# DB_Main-X01.net
KiCad netlist of a schematic drawn in Altium Designer
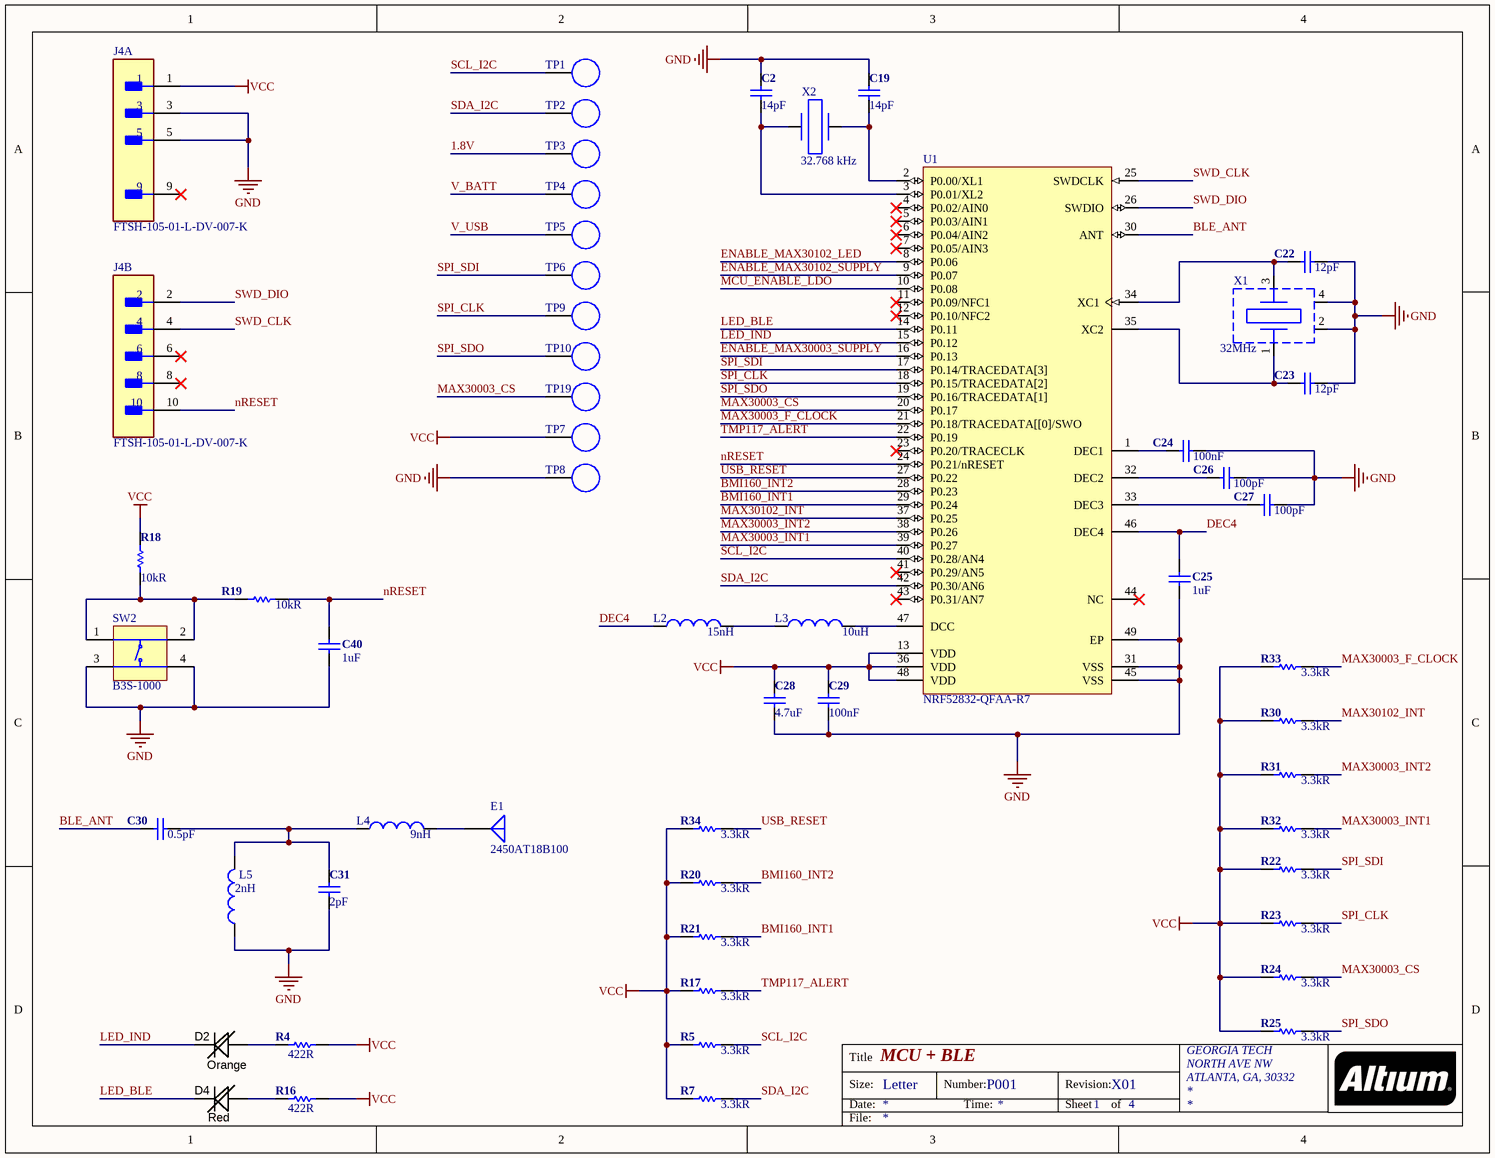
[diagram p0: DB_Main-X01.SchDoc]

(export (version "E")
  (design (tool "Eeschema 10.0.6"))
  (components
    (comp (ref "C2")
      (value "14pF")
      (footprint "C0402")
      (fields
        (field (name "MANUFACTURER") "Kyocera AVX")
        (field (name "MANUFACTURER PART NUMBER") "04025U140FAT2A")
        (field (name "TOLERANCE") "1%")
      )
      (libsource (lib "DB-X01") (part "C-0402(1005)"))
    )
    (comp (ref "C19")
      (value "14pF")
      (footprint "C0402")
      (fields
        (field (name "MANUFACTURER") "Kyocera AVX")
        (field (name "MANUFACTURER PART NUMBER") "04025U140FAT2A")
        (field (name "TOLERANCE") "1%")
      )
      (libsource (lib "DB-X01") (part "C-0402(1005)"))
    )
    (comp (ref "C22")
      (value "12pF")
      (footprint "C0402")
      (fields
        (field (name "MANUFACTURER") "Kyocera AVX")
        (field (name "MANUFACTURER PART NUMBER") "04025U120FAT2A")
        (field (name "TOLERANCE") "1%")
      )
      (libsource (lib "DB-X01") (part "C-0402(1005)"))
    )
    (comp (ref "C23")
      (value "12pF")
      (footprint "C0402")
      (fields
        (field (name "MANUFACTURER") "Kyocera AVX")
        (field (name "MANUFACTURER PART NUMBER") "04025U120FAT2A")
        (field (name "TOLERANCE") "1%")
      )
      (libsource (lib "DB-X01") (part "C-0402(1005)"))
    )
    (comp (ref "C24")
      (value "100nF")
      (footprint "C0402")
      (fields
        (field (name "MANUFACTURER") "Taiyo Yuden")
        (field (name "MANUFACTURER PART NUMBER") "TMK105BJ104KV-F")
        (field (name "TOLERANCE") "10%")
      )
      (libsource (lib "DB-X01") (part "C-0402(1005)"))
    )
    (comp (ref "C25")
      (value "1uF")
      (footprint "C0402")
      (fields
        (field (name "MANUFACTURER") "Yageo")
        (field (name "MANUFACTURER PART NUMBER") "CC0402MRX5R5BB105")
        (field (name "TOLERANCE") "20%")
      )
      (libsource (lib "DB-X01") (part "C-0402(1005)"))
    )
    (comp (ref "C26")
      (value "100pF")
      (footprint "C0402")
      (fields
        (field (name "MANUFACTURER") "Yageo")
        (field (name "MANUFACTURER PART NUMBER") "CC0402FRNPO9BN101")
        (field (name "TOLERANCE") "1%")
      )
      (libsource (lib "DB-X01") (part "C-0402(1005)"))
    )
    (comp (ref "C27")
      (value "100pF")
      (footprint "C0402")
      (fields
        (field (name "MANUFACTURER") "Yageo")
        (field (name "MANUFACTURER PART NUMBER") "CC0402FRNPO9BN101")
        (field (name "TOLERANCE") "1%")
      )
      (libsource (lib "DB-X01") (part "C-0402(1005)"))
    )
    (comp (ref "C28")
      (value "4.7uF")
      (footprint "C0402")
      (description "0402 10 V 4.7 uF ±20% Tolerance X5R Multilayer Ceramic Chip Capacitor")
      (fields
        (field (name "MANUFACTURER") "Murata")
        (field (name "MANUFACTURER PART NUMBER") "GRM155R61A475MEAAD")
      )
      (libsource (lib "DB-X01") (part "C-0402(1005)"))
    )
    (comp (ref "C29")
      (value "100nF")
      (footprint "C0603")
      (fields
        (field (name "MANUFACTURER") "Yageo")
        (field (name "MANUFACTURER PART NUMBER") "CC0402ZRY5V8BB104")
        (field (name "TOLERANCE") "80%")
      )
      (libsource (lib "DB-X01") (part "C-0603(1608)"))
    )
    (comp (ref "C30")
      (value "0.5pF")
      (footprint "C0402")
      (fields
        (field (name "MANUFACTURER") "Murata")
        (field (name "MANUFACTURER PART NUMBER") "GJM1555C1HR50WB01D")
        (field (name "VOLTAGE") "50V")
      )
      (libsource (lib "DB-X01") (part "C-0402(1005)"))
    )
    (comp (ref "C31")
      (value "2pF")
      (footprint "C0402")
      (fields
        (field (name "MANUFACTURER") "Murata")
        (field (name "MANUFACTURER PART NUMBER") "GJM1555C1H2R0BB01D")
      )
      (libsource (lib "DB-X01") (part "C-0402(1005)"))
    )
    (comp (ref "C40")
      (value "1uF")
      (footprint "C0402")
      (fields
        (field (name "MANUFACTURER") "Yageo")
        (field (name "MANUFACTURER PART NUMBER") "CC0402MRX5R5BB105")
        (field (name "TOLERANCE") "20%")
      )
      (libsource (lib "DB-X01") (part "C-0402(1005)"))
    )
    (comp (ref "D2")
      (value "Orange")
      (footprint "LED_0402")
      (description "Single Color LED, Super Bright Orange, Water Clear, 0.8mm")
      (fields
        (field (name "MANUFACTURER") "Kingbright")
        (field (name "MANUFACTURER PART NUMBER") "APHHS1005SECK")
      )
      (libsource (lib "DB-X01") (part "LED_0402(1005)"))
    )
    (comp (ref "D4")
      (value "Red")
      (footprint "LED_0402")
      (description "Single Color LED, Hyper Red, Water Clear, 0.8mm")
      (fields
        (field (name "MANUFACTURER") "Kingbright")
        (field (name "MANUFACTURER PART NUMBER") "APHHS1005SURCK")
      )
      (libsource (lib "DB-X01") (part "LED_0402(1005)"))
    )
    (comp (ref "E1")
      (value "2450AT18B100")
      (footprint "2450AT18B100")
      (description "2.4 GHz BLE Antenna")
      (fields
        (field (name "MANUFACTURER") "Johanson")
        (field (name "MANUFACTURER PART NUMBER") "2450AT18B100E")
      )
      (libsource (lib "DB-X01") (part "2450AT18B100"))
    )
    (comp (ref "J4")
      (value "FTSH-105-01-L-DV-007-K")
      (footprint "FTSH-105-01-L-DV-007-K")
      (description "CONN HEADER SMD 10POS 1.27MM")
      (fields (field (name "MANUFACTURER") "Samtec"))
      (libsource (lib "DB-X01") (part "7c368be3265735b2816d0cab4417f87"))
    )
    (comp (ref "L2")
      (value "15nH")
      (footprint "L0402")
      (description "General Purpose Inductor, 0.015uH, 5%, 1 Element, Ferrite-Core, SMD, 0402")
      (fields
        (field (name "MANUFACTURER") "Taiyo Yuden")
        (field (name "MANUFACTURER PART NUMBER") "HK100515NJ-T")
      )
      (libsource (lib "DB-X01") (part "I-0402(1005)"))
    )
    (comp (ref "L3")
      (value "10uH")
      (footprint "L0603")
      (description "General Purpose Inductor, 10uH, 10%, 1 Element, Ferrite-Core, SMD, 0603")
      (fields
        (field (name "MANUFACTURER") "Taiyo Yuden")
        (field (name "MANUFACTURER PART NUMBER") "CBMF1608T100K")
      )
      (libsource (lib "DB-X01") (part "I-0603(1608)"))
    )
    (comp (ref "L4")
      (value "9nH")
      (footprint "L0402")
      (description "General Purpose Inductor, 0.009uH, 2%, 1 Element, SMD")
      (fields
        (field (name "MANUFACTURER") "Murata")
        (field (name "MANUFACTURER PART NUMBER") "LQW15AN9N0G80D")
      )
      (libsource (lib "DB-X01") (part "I-0402(1005)"))
    )
    (comp (ref "L5")
      (value "2nH")
      (footprint "L0402")
      (description "General Purpose Inductor, 0.002uH, 5%, 1 Element, Ceramic-Core, SMD, 0402")
      (fields
        (field (name "MANUFACTURER") "Abracon")
        (field (name "MANUFACTURER PART NUMBER") "AISC-0402-2N0J-T")
      )
      (libsource (lib "DB-X01") (part "I-0402(1005)"))
    )
    (comp (ref "R4")
      (value "422R")
      (footprint "R0402")
      (description "Fixed Resistor, Thin Film, 0.0625W, 422ohm, 50V, 0.1% +/-Tol, 25ppm/Cel, Surface Mount, 0402")
      (fields
        (field (name "MANUFACTURER") "Yageo")
        (field (name "MANUFACTURER PART NUMBER") "RT0402BRD07422RL")
      )
      (libsource (lib "DB-X01") (part "R-0402(1005)"))
    )
    (comp (ref "R5")
      (value "3.3kR")
      (footprint "R0402")
      (fields
        (field (name "MANUFACTURER") "Yageo")
        (field (name "MANUFACTURER PART NUMBER") "AC0402FR-073K3L")
        (field (name "TOLERANCE") "1%")
      )
      (libsource (lib "DB-X01") (part "R-0402(1005)"))
    )
    (comp (ref "R7")
      (value "3.3kR")
      (footprint "R0402")
      (fields
        (field (name "MANUFACTURER") "Yageo")
        (field (name "MANUFACTURER PART NUMBER") "AC0402FR-073K3L")
        (field (name "TOLERANCE") "1%")
      )
      (libsource (lib "DB-X01") (part "R-0402(1005)"))
    )
    (comp (ref "R16")
      (value "422R")
      (footprint "R0402")
      (description "Fixed Resistor, Thin Film, 0.0625W, 422ohm, 50V, 0.1% +/-Tol, 25ppm/Cel, Surface Mount, 0402")
      (fields
        (field (name "MANUFACTURER") "Yageo")
        (field (name "MANUFACTURER PART NUMBER") "RT0402BRD07422RL")
      )
      (libsource (lib "DB-X01") (part "R-0402(1005)"))
    )
    (comp (ref "R17")
      (value "3.3kR")
      (footprint "R0402")
      (fields
        (field (name "MANUFACTURER") "Yageo")
        (field (name "MANUFACTURER PART NUMBER") "AC0402FR-073K3L")
        (field (name "TOLERANCE") "1%")
      )
      (libsource (lib "DB-X01") (part "R-0402(1005)"))
    )
    (comp (ref "R18")
      (value "10kR")
      (footprint "R0402")
      (fields
        (field (name "MANUFACTURER") "Yageo")
        (field (name "MANUFACTURER PART NUMBER") "AC0402FR-0710KL")
        (field (name "TOLERANCE") "1%")
      )
      (libsource (lib "DB-X01") (part "R-0402(1005)"))
    )
    (comp (ref "R19")
      (value "10kR")
      (footprint "R0402")
      (fields
        (field (name "MANUFACTURER") "Yageo")
        (field (name "MANUFACTURER PART NUMBER") "AC0402FR-0710KL")
        (field (name "TOLERANCE") "1%")
      )
      (libsource (lib "DB-X01") (part "R-0402(1005)"))
    )
    (comp (ref "R20")
      (value "3.3kR")
      (footprint "R0402")
      (fields
        (field (name "MANUFACTURER") "Yageo")
        (field (name "MANUFACTURER PART NUMBER") "AC0402FR-073K3L")
        (field (name "TOLERANCE") "1%")
      )
      (libsource (lib "DB-X01") (part "R-0402(1005)"))
    )
    (comp (ref "R21")
      (value "3.3kR")
      (footprint "R0402")
      (fields
        (field (name "MANUFACTURER") "Yageo")
        (field (name "MANUFACTURER PART NUMBER") "AC0402FR-073K3L")
        (field (name "TOLERANCE") "1%")
      )
      (libsource (lib "DB-X01") (part "R-0402(1005)"))
    )
    (comp (ref "R22")
      (value "3.3kR")
      (footprint "R0402")
      (fields
        (field (name "MANUFACTURER") "Yageo")
        (field (name "MANUFACTURER PART NUMBER") "AC0402FR-073K3L")
        (field (name "TOLERANCE") "1%")
      )
      (libsource (lib "DB-X01") (part "R-0402(1005)"))
    )
    (comp (ref "R23")
      (value "3.3kR")
      (footprint "R0402")
      (fields
        (field (name "MANUFACTURER") "Yageo")
        (field (name "MANUFACTURER PART NUMBER") "AC0402FR-073K3L")
        (field (name "TOLERANCE") "1%")
      )
      (libsource (lib "DB-X01") (part "R-0402(1005)"))
    )
    (comp (ref "R24")
      (value "3.3kR")
      (footprint "R0402")
      (fields
        (field (name "MANUFACTURER") "Yageo")
        (field (name "MANUFACTURER PART NUMBER") "AC0402FR-073K3L")
        (field (name "TOLERANCE") "1%")
      )
      (libsource (lib "DB-X01") (part "R-0402(1005)"))
    )
    (comp (ref "R25")
      (value "3.3kR")
      (footprint "R0402")
      (fields
        (field (name "MANUFACTURER") "Yageo")
        (field (name "MANUFACTURER PART NUMBER") "AC0402FR-073K3L")
        (field (name "TOLERANCE") "1%")
      )
      (libsource (lib "DB-X01") (part "R-0402(1005)"))
    )
    (comp (ref "R30")
      (value "3.3kR")
      (footprint "R0402")
      (fields
        (field (name "MANUFACTURER") "Yageo")
        (field (name "MANUFACTURER PART NUMBER") "AC0402FR-073K3L")
        (field (name "TOLERANCE") "1%")
      )
      (libsource (lib "DB-X01") (part "R-0402(1005)"))
    )
    (comp (ref "R31")
      (value "3.3kR")
      (footprint "R0402")
      (fields
        (field (name "MANUFACTURER") "Yageo")
        (field (name "MANUFACTURER PART NUMBER") "AC0402FR-073K3L")
        (field (name "TOLERANCE") "1%")
      )
      (libsource (lib "DB-X01") (part "R-0402(1005)"))
    )
    (comp (ref "R32")
      (value "3.3kR")
      (footprint "R0402")
      (fields
        (field (name "MANUFACTURER") "Yageo")
        (field (name "MANUFACTURER PART NUMBER") "AC0402FR-073K3L")
        (field (name "TOLERANCE") "1%")
      )
      (libsource (lib "DB-X01") (part "R-0402(1005)"))
    )
    (comp (ref "R33")
      (value "3.3kR")
      (footprint "R0402")
      (fields
        (field (name "MANUFACTURER") "Yageo")
        (field (name "MANUFACTURER PART NUMBER") "AC0402FR-073K3L")
        (field (name "TOLERANCE") "1%")
      )
      (libsource (lib "DB-X01") (part "R-0402(1005)"))
    )
    (comp (ref "R34")
      (value "3.3kR")
      (footprint "R0402")
      (fields
        (field (name "MANUFACTURER") "Yageo")
        (field (name "MANUFACTURER PART NUMBER") "AC0402FR-073K3L")
        (field (name "TOLERANCE") "1%")
      )
      (libsource (lib "DB-X01") (part "R-0402(1005)"))
    )
    (comp (ref "SW2")
      (value "B3S-1000")
      (footprint "OMRON-B3S-1000-4_V")
      (description "Sealed Tactile Switch, SPST-NO, 3 to 24 V, -25 to 70 degC, 4-Pin SMD, RoHS, Bulk")
      (fields (field (name "MANUFACTURER") "Omron") (field (name "MANUFACTURER PART NUMBER") "B3S-1000P"))
      (libsource (lib "Altium Content Vault") (part "SW-SPST-4_A"))
    )
    (comp (ref "TP1")
      (value "S1751-46R")
      (footprint "S1751-46R")
      (description "PC TEST POINT TIN SMD")
      (fields (field (name "MANUFACTURER") "Harwin Inc."))
      (libsource (lib "DB-X01") (part "S1751-46R"))
    )
    (comp (ref "TP2")
      (value "S1751-46R")
      (footprint "S1751-46R")
      (description "PC TEST POINT TIN SMD")
      (fields (field (name "MANUFACTURER") "Harwin Inc."))
      (libsource (lib "DB-X01") (part "S1751-46R"))
    )
    (comp (ref "TP3")
      (value "S1751-46R")
      (footprint "S1751-46R")
      (description "PC TEST POINT TIN SMD")
      (fields (field (name "MANUFACTURER") "Harwin Inc."))
      (libsource (lib "DB-X01") (part "S1751-46R"))
    )
    (comp (ref "TP4")
      (value "S1751-46R")
      (footprint "S1751-46R")
      (description "PC TEST POINT TIN SMD")
      (fields (field (name "MANUFACTURER") "Harwin Inc."))
      (libsource (lib "DB-X01") (part "S1751-46R"))
    )
    (comp (ref "TP5")
      (value "S1751-46R")
      (footprint "S1751-46R")
      (description "PC TEST POINT TIN SMD")
      (fields (field (name "MANUFACTURER") "Harwin Inc."))
      (libsource (lib "DB-X01") (part "S1751-46R"))
    )
    (comp (ref "TP6")
      (value "S1751-46R")
      (footprint "S1751-46R")
      (description "PC TEST POINT TIN SMD")
      (fields (field (name "MANUFACTURER") "Harwin Inc."))
      (libsource (lib "DB-X01") (part "S1751-46R"))
    )
    (comp (ref "TP7")
      (value "S1751-46R")
      (footprint "S1751-46R")
      (description "PC TEST POINT TIN SMD")
      (fields (field (name "MANUFACTURER") "Harwin Inc."))
      (libsource (lib "DB-X01") (part "S1751-46R"))
    )
    (comp (ref "TP8")
      (value "S1751-46R")
      (footprint "S1751-46R")
      (description "PC TEST POINT TIN SMD")
      (fields (field (name "MANUFACTURER") "Harwin Inc."))
      (libsource (lib "DB-X01") (part "S1751-46R"))
    )
    (comp (ref "TP9")
      (value "S1751-46R")
      (footprint "S1751-46R")
      (description "PC TEST POINT TIN SMD")
      (fields (field (name "MANUFACTURER") "Harwin Inc."))
      (libsource (lib "DB-X01") (part "S1751-46R"))
    )
    (comp (ref "TP10")
      (value "S1751-46R")
      (footprint "S1751-46R")
      (description "PC TEST POINT TIN SMD")
      (fields (field (name "MANUFACTURER") "Harwin Inc."))
      (libsource (lib "DB-X01") (part "S1751-46R"))
    )
    (comp (ref "TP19")
      (value "S1751-46R")
      (footprint "S1751-46R")
      (description "PC TEST POINT TIN SMD")
      (fields (field (name "MANUFACTURER") "Harwin Inc."))
      (libsource (lib "DB-X01") (part "S1751-46R"))
    )
    (comp (ref "U1")
      (value "NRF52832-QFAA-R7")
      (footprint "NRF52832-QFAA-R7")
      (fields (field (name "MANUFACTURER") "Nordic Semiconductor"))
      (libsource (lib "DB-X01") (part "NRSC-NRF52832-QF-48"))
    )
    (comp (ref "X1")
      (value "32MHz")
      (footprint "CRYSTAL_1MM6_X_1MM2")
      (description "Parallel - Fundamental Quartz Crystal, 32MHz Nom")
      (fields (field (name "MANUFACTURER") "Diodes") (field (name "MANUFACTURER PART NUMBER") "US3200005Z"))
      (libsource (lib "DB-X01") (part "CRYSTAL_32MHz"))
    )
    (comp (ref "X2")
      (value "32.768 kHz")
      (footprint "CRYSTAL_1MM2_X_1MM0")
      (description "Parallel - Fundamental Quartz Crystal, 0.032768MHz Nom")
      (fields
        (field (name "MANUFACTURER") "ECS International")
        (field (name "MANUFACTURER PART NUMBER") "ECS-.327-9-1210-TR")
      )
      (libsource (lib "DB-X01") (part "CRYSTAL_32K768"))
    )
  )
  (nets
    (net (code "1") (name "/1.8V") (class "Default")
      (node (ref "TP3") (pin "1") (pinfunction "1_1") (pintype "passive"))
    )
    (net (code "2") (name "/BLE_ANT") (class "Default")
      (node (ref "C30") (pin "1") (pinfunction "1_1") (pintype "passive"))
      (node (ref "U1") (pin "30") (pinfunction "ANT_30") (pintype "bidirectional"))
    )
    (net (code "3") (name "/BMI160_INT1") (class "Default")
      (node (ref "R21") (pin "2") (pinfunction "2_2") (pintype "passive"))
      (node (ref "U1") (pin "29") (pinfunction "P0.24_29") (pintype "bidirectional"))
    )
    (net (code "4") (name "/BMI160_INT2") (class "Default")
      (node (ref "R20") (pin "2") (pinfunction "2_2") (pintype "passive"))
      (node (ref "U1") (pin "28") (pinfunction "P0.23_28") (pintype "bidirectional"))
    )
    (net (code "5") (name "/DEC4") (class "Default")
      (node (ref "C25") (pin "2") (pinfunction "2_2") (pintype "passive"))
      (node (ref "L2") (pin "1") (pinfunction "1_1") (pintype "passive"))
      (node (ref "U1") (pin "46") (pinfunction "DEC4_46") (pintype "passive"))
    )
    (net (code "6") (name "/ENABLE_MAX30003_SUPPLY") (class "Default")
      (node (ref "U1") (pin "16") (pinfunction "P0.13_16") (pintype "bidirectional"))
    )
    (net (code "7") (name "/ENABLE_MAX30102_LED") (class "Default")
      (node (ref "U1") (pin "8") (pinfunction "P0.06_8") (pintype "bidirectional"))
    )
    (net (code "8") (name "/ENABLE_MAX30102_SUPPLY") (class "Default")
      (node (ref "U1") (pin "9") (pinfunction "P0.07_9") (pintype "bidirectional"))
    )
    (net (code "9") (name "/LED_BLE") (class "Default")
      (node (ref "D4") (pin "K") (pinfunction "K_K") (pintype "passive"))
      (node (ref "U1") (pin "14") (pinfunction "P0.11_14") (pintype "bidirectional"))
    )
    (net (code "10") (name "/LED_IND") (class "Default")
      (node (ref "D2") (pin "K") (pinfunction "K_K") (pintype "passive"))
      (node (ref "U1") (pin "15") (pinfunction "P0.12_15") (pintype "bidirectional"))
    )
    (net (code "11") (name "/MAX30003_CS") (class "Default")
      (node (ref "R24") (pin "2") (pinfunction "2_2") (pintype "passive"))
      (node (ref "TP19") (pin "1") (pinfunction "1_1") (pintype "passive"))
      (node (ref "U1") (pin "20") (pinfunction "P0.17_20") (pintype "bidirectional"))
    )
    (net (code "12") (name "/MAX30003_F_CLOCK") (class "Default")
      (node (ref "R33") (pin "2") (pinfunction "2_2") (pintype "passive"))
      (node (ref "U1") (pin "21") (pinfunction "P0.18/TRACEDATA[[0]/SWO_21") (pintype "bidirectional"))
    )
    (net (code "13") (name "/MAX30003_INT1") (class "Default")
      (node (ref "R32") (pin "2") (pinfunction "2_2") (pintype "passive"))
      (node (ref "U1") (pin "39") (pinfunction "P0.27_39") (pintype "bidirectional"))
    )
    (net (code "14") (name "/MAX30003_INT2") (class "Default")
      (node (ref "R31") (pin "2") (pinfunction "2_2") (pintype "passive"))
      (node (ref "U1") (pin "38") (pinfunction "P0.26_38") (pintype "bidirectional"))
    )
    (net (code "15") (name "/MAX30102_INT") (class "Default")
      (node (ref "R30") (pin "2") (pinfunction "2_2") (pintype "passive"))
      (node (ref "U1") (pin "37") (pinfunction "P0.25_37") (pintype "bidirectional"))
    )
    (net (code "16") (name "/MCU_ENABLE_LDO") (class "Default")
      (node (ref "U1") (pin "10") (pinfunction "P0.08_10") (pintype "bidirectional"))
    )
    (net (code "17") (name "/SCL_I2C") (class "Default")
      (node (ref "R5") (pin "2") (pinfunction "2_2") (pintype "passive"))
      (node (ref "TP1") (pin "1") (pinfunction "1_1") (pintype "passive"))
      (node (ref "U1") (pin "40") (pinfunction "P0.28/AN4_40") (pintype "bidirectional"))
    )
    (net (code "18") (name "/SDA_I2C") (class "Default")
      (node (ref "R7") (pin "2") (pinfunction "2_2") (pintype "passive"))
      (node (ref "TP2") (pin "1") (pinfunction "1_1") (pintype "passive"))
      (node (ref "U1") (pin "42") (pinfunction "P0.30/AN6_42") (pintype "bidirectional"))
    )
    (net (code "19") (name "/SPI_CLK") (class "Default")
      (node (ref "R23") (pin "2") (pinfunction "2_2") (pintype "passive"))
      (node (ref "TP9") (pin "1") (pinfunction "1_1") (pintype "passive"))
      (node (ref "U1") (pin "18") (pinfunction "P0.15/TRACEDATA[2]_18") (pintype "bidirectional"))
    )
    (net (code "20") (name "/SPI_SDI") (class "Default")
      (node (ref "R22") (pin "2") (pinfunction "2_2") (pintype "passive"))
      (node (ref "TP6") (pin "1") (pinfunction "1_1") (pintype "passive"))
      (node (ref "U1") (pin "17") (pinfunction "P0.14/TRACEDATA[3]_17") (pintype "bidirectional"))
    )
    (net (code "21") (name "/SPI_SDO") (class "Default")
      (node (ref "R25") (pin "2") (pinfunction "2_2") (pintype "passive"))
      (node (ref "TP10") (pin "1") (pinfunction "1_1") (pintype "passive"))
      (node (ref "U1") (pin "19") (pinfunction "P0.16/TRACEDATA[1]_19") (pintype "bidirectional"))
    )
    (net (code "22") (name "/SWD_CLK") (class "Default")
      (node (ref "J4") (pin "4") (pinfunction "4_4") (pintype "passive"))
      (node (ref "U1") (pin "25") (pinfunction "SWDCLK_25") (pintype "input"))
    )
    (net (code "23") (name "/SWD_DIO") (class "Default")
      (node (ref "J4") (pin "2") (pinfunction "2_2") (pintype "passive"))
      (node (ref "U1") (pin "26") (pinfunction "SWDIO_26") (pintype "bidirectional"))
    )
    (net (code "24") (name "/TMP117_ALERT") (class "Default")
      (node (ref "R17") (pin "2") (pinfunction "2_2") (pintype "passive"))
      (node (ref "U1") (pin "22") (pinfunction "P0.19_22") (pintype "bidirectional"))
    )
    (net (code "25") (name "/USB_RESET") (class "Default")
      (node (ref "R34") (pin "2") (pinfunction "2_2") (pintype "passive"))
      (node (ref "U1") (pin "27") (pinfunction "P0.22_27") (pintype "bidirectional"))
    )
    (net (code "26") (name "/V_BATT") (class "Default")
      (node (ref "TP4") (pin "1") (pinfunction "1_1") (pintype "passive"))
    )
    (net (code "27") (name "/V_USB") (class "Default")
      (node (ref "TP5") (pin "1") (pinfunction "1_1") (pintype "passive"))
    )
    (net (code "28") (name "/nRESET") (class "Default")
      (node (ref "C40") (pin "2") (pinfunction "2_2") (pintype "passive"))
      (node (ref "J4") (pin "10") (pinfunction "10_10") (pintype "passive"))
      (node (ref "R19") (pin "2") (pinfunction "2_2") (pintype "passive"))
      (node (ref "U1") (pin "24") (pinfunction "P0.21/nRESET_24") (pintype "bidirectional"))
    )
    (net (code "29") (name "GND") (class "Default")
      (node (ref "C19") (pin "1") (pinfunction "1_1") (pintype "passive"))
      (node (ref "C2") (pin "1") (pinfunction "1_1") (pintype "passive"))
      (node (ref "C22") (pin "2") (pinfunction "2_2") (pintype "passive"))
      (node (ref "C23") (pin "2") (pinfunction "2_2") (pintype "passive"))
      (node (ref "C24") (pin "2") (pinfunction "2_2") (pintype "passive"))
      (node (ref "C25") (pin "1") (pinfunction "1_1") (pintype "passive"))
      (node (ref "C26") (pin "2") (pinfunction "2_2") (pintype "passive"))
      (node (ref "C27") (pin "2") (pinfunction "2_2") (pintype "passive"))
      (node (ref "C28") (pin "2") (pinfunction "2_2") (pintype "passive"))
      (node (ref "C29") (pin "1") (pinfunction "1_1") (pintype "passive"))
      (node (ref "C31") (pin "2") (pinfunction "2_2") (pintype "passive"))
      (node (ref "C40") (pin "1") (pinfunction "1_1") (pintype "passive"))
      (node (ref "J4") (pin "3") (pinfunction "3_3") (pintype "passive"))
      (node (ref "J4") (pin "5") (pinfunction "5_5") (pintype "passive"))
      (node (ref "L5") (pin "1") (pinfunction "1_1") (pintype "passive"))
      (node (ref "SW2") (pin "3") (pinfunction "3_3") (pintype "passive"))
      (node (ref "SW2") (pin "4") (pinfunction "4_4") (pintype "passive"))
      (node (ref "TP8") (pin "1") (pinfunction "1_1") (pintype "passive"))
      (node (ref "U1") (pin "31") (pinfunction "VSS_31") (pintype "power_in"))
      (node (ref "U1") (pin "45") (pinfunction "VSS_45") (pintype "power_in"))
      (node (ref "U1") (pin "49") (pinfunction "EP_49") (pintype "power_in"))
      (node (ref "X1") (pin "2") (pinfunction "GND_2") (pintype "passive"))
      (node (ref "X1") (pin "4") (pinfunction "GND_4") (pintype "passive"))
    )
    (net (code "30") (name "Net-(C30-Pad2)") (class "Default")
      (node (ref "C30") (pin "2") (pinfunction "2_2") (pintype "passive"))
      (node (ref "C31") (pin "1") (pinfunction "1_1") (pintype "passive"))
      (node (ref "L4") (pin "1") (pinfunction "1_1") (pintype "passive"))
      (node (ref "L5") (pin "2") (pinfunction "2_2") (pintype "passive"))
    )
    (net (code "31") (name "Net-(D2-PadA)") (class "Default")
      (node (ref "D2") (pin "A") (pinfunction "A_A") (pintype "passive"))
      (node (ref "R4") (pin "2") (pinfunction "2_2") (pintype "passive"))
    )
    (net (code "32") (name "Net-(D4-PadA)") (class "Default")
      (node (ref "D4") (pin "A") (pinfunction "A_A") (pintype "passive"))
      (node (ref "R16") (pin "2") (pinfunction "2_2") (pintype "passive"))
    )
    (net (code "33") (name "Net-(E1-A)") (class "Default")
      (node (ref "E1") (pin "1") (pinfunction "A_1") (pintype "passive"))
      (node (ref "L4") (pin "2") (pinfunction "2_2") (pintype "passive"))
    )
    (net (code "34") (name "Net-(L2-Pad2)") (class "Default")
      (node (ref "L2") (pin "2") (pinfunction "2_2") (pintype "passive"))
      (node (ref "L3") (pin "1") (pinfunction "1_1") (pintype "passive"))
    )
    (net (code "35") (name "Net-(R18-Pad2)") (class "Default")
      (node (ref "R18") (pin "2") (pinfunction "2_2") (pintype "passive"))
      (node (ref "R19") (pin "1") (pinfunction "1_1") (pintype "passive"))
      (node (ref "SW2") (pin "1") (pinfunction "1_1") (pintype "passive"))
      (node (ref "SW2") (pin "2") (pinfunction "2_2") (pintype "passive"))
    )
    (net (code "36") (name "Net-(U1-DCC)") (class "Default")
      (node (ref "L3") (pin "2") (pinfunction "2_2") (pintype "passive"))
      (node (ref "U1") (pin "47") (pinfunction "DCC_47") (pintype "power_in"))
    )
    (net (code "37") (name "Net-(U1-DEC1)") (class "Default")
      (node (ref "C24") (pin "1") (pinfunction "1_1") (pintype "passive"))
      (node (ref "U1") (pin "1") (pinfunction "DEC1_1") (pintype "passive"))
    )
    (net (code "38") (name "Net-(U1-DEC2)") (class "Default")
      (node (ref "C26") (pin "1") (pinfunction "1_1") (pintype "passive"))
      (node (ref "U1") (pin "32") (pinfunction "DEC2_32") (pintype "passive"))
    )
    (net (code "39") (name "Net-(U1-DEC3)") (class "Default")
      (node (ref "C27") (pin "1") (pinfunction "1_1") (pintype "passive"))
      (node (ref "U1") (pin "33") (pinfunction "DEC3_33") (pintype "passive"))
    )
    (net (code "40") (name "Net-(U1-P0.00{slash}XL1)") (class "Default")
      (node (ref "C19") (pin "2") (pinfunction "2_2") (pintype "passive"))
      (node (ref "U1") (pin "2") (pinfunction "P0.00/XL1_2") (pintype "bidirectional"))
      (node (ref "X2") (pin "2") (pinfunction "2_2") (pintype "passive"))
    )
    (net (code "41") (name "Net-(U1-P0.01{slash}XL2)") (class "Default")
      (node (ref "C2") (pin "2") (pinfunction "2_2") (pintype "passive"))
      (node (ref "U1") (pin "3") (pinfunction "P0.01/XL2_3") (pintype "bidirectional"))
      (node (ref "X2") (pin "1") (pinfunction "1_1") (pintype "passive"))
    )
    (net (code "42") (name "Net-(U1-XC1)") (class "Default")
      (node (ref "C22") (pin "1") (pinfunction "1_1") (pintype "passive"))
      (node (ref "U1") (pin "34") (pinfunction "XC1_34") (pintype "input"))
      (node (ref "X1") (pin "3") (pinfunction "3_3") (pintype "passive"))
    )
    (net (code "43") (name "Net-(U1-XC2)") (class "Default")
      (node (ref "C23") (pin "1") (pinfunction "1_1") (pintype "passive"))
      (node (ref "U1") (pin "35") (pinfunction "XC2_35") (pintype "passive"))
      (node (ref "X1") (pin "1") (pinfunction "1_1") (pintype "passive"))
    )
    (net (code "44") (name "VCC") (class "Default")
      (node (ref "C28") (pin "1") (pinfunction "1_1") (pintype "passive"))
      (node (ref "C29") (pin "2") (pinfunction "2_2") (pintype "passive"))
      (node (ref "J4") (pin "1") (pinfunction "1_1") (pintype "passive"))
      (node (ref "R16") (pin "1") (pinfunction "1_1") (pintype "passive"))
      (node (ref "R17") (pin "1") (pinfunction "1_1") (pintype "passive"))
      (node (ref "R18") (pin "1") (pinfunction "1_1") (pintype "passive"))
      (node (ref "R20") (pin "1") (pinfunction "1_1") (pintype "passive"))
      (node (ref "R21") (pin "1") (pinfunction "1_1") (pintype "passive"))
      (node (ref "R22") (pin "1") (pinfunction "1_1") (pintype "passive"))
      (node (ref "R23") (pin "1") (pinfunction "1_1") (pintype "passive"))
      (node (ref "R24") (pin "1") (pinfunction "1_1") (pintype "passive"))
      (node (ref "R25") (pin "1") (pinfunction "1_1") (pintype "passive"))
      (node (ref "R30") (pin "1") (pinfunction "1_1") (pintype "passive"))
      (node (ref "R31") (pin "1") (pinfunction "1_1") (pintype "passive"))
      (node (ref "R32") (pin "1") (pinfunction "1_1") (pintype "passive"))
      (node (ref "R33") (pin "1") (pinfunction "1_1") (pintype "passive"))
      (node (ref "R34") (pin "1") (pinfunction "1_1") (pintype "passive"))
      (node (ref "R4") (pin "1") (pinfunction "1_1") (pintype "passive"))
      (node (ref "R5") (pin "1") (pinfunction "1_1") (pintype "passive"))
      (node (ref "R7") (pin "1") (pinfunction "1_1") (pintype "passive"))
      (node (ref "TP7") (pin "1") (pinfunction "1_1") (pintype "passive"))
      (node (ref "U1") (pin "13") (pinfunction "VDD_13") (pintype "power_in"))
      (node (ref "U1") (pin "36") (pinfunction "VDD_36") (pintype "power_in"))
      (node (ref "U1") (pin "48") (pinfunction "VDD_48") (pintype "power_in"))
    )
    (net (code "45") (name "unconnected-(J4-Pad6)") (class "Default")
      (node (ref "J4") (pin "6") (pinfunction "6_6") (pintype "passive+no_connect"))
    )
    (net (code "46") (name "unconnected-(J4-Pad8)") (class "Default")
      (node (ref "J4") (pin "8") (pinfunction "8_8") (pintype "passive+no_connect"))
    )
    (net (code "47") (name "unconnected-(J4-Pad9)") (class "Default")
      (node (ref "J4") (pin "9") (pinfunction "9_9") (pintype "passive+no_connect"))
    )
    (net (code "48") (name "unconnected-(U1-NC-Pad44)") (class "Default")
      (node (ref "U1") (pin "44") (pinfunction "NC_44") (pintype "passive+no_connect"))
    )
    (net (code "49") (name "unconnected-(U1-P0.02{slash}AIN0-Pad4)") (class "Default")
      (node (ref "U1") (pin "4") (pinfunction "P0.02/AIN0_4") (pintype "bidirectional+no_connect"))
    )
    (net (code "50") (name "unconnected-(U1-P0.03{slash}AIN1-Pad5)") (class "Default")
      (node (ref "U1") (pin "5") (pinfunction "P0.03/AIN1_5") (pintype "bidirectional+no_connect"))
    )
    (net (code "51") (name "unconnected-(U1-P0.04{slash}AIN2-Pad6)") (class "Default")
      (node (ref "U1") (pin "6") (pinfunction "P0.04/AIN2_6") (pintype "bidirectional+no_connect"))
    )
    (net (code "52") (name "unconnected-(U1-P0.05{slash}AIN3-Pad7)") (class "Default")
      (node (ref "U1") (pin "7") (pinfunction "P0.05/AIN3_7") (pintype "bidirectional+no_connect"))
    )
    (net (code "53") (name "unconnected-(U1-P0.09{slash}NFC1-Pad11)") (class "Default")
      (node (ref "U1") (pin "11") (pinfunction "P0.09/NFC1_11") (pintype "bidirectional+no_connect"))
    )
    (net (code "54") (name "unconnected-(U1-P0.10{slash}NFC2-Pad12)") (class "Default")
      (node (ref "U1") (pin "12") (pinfunction "P0.10/NFC2_12") (pintype "bidirectional+no_connect"))
    )
    (net (code "55") (name "unconnected-(U1-P0.20{slash}TRACECLK-Pad23)") (class "Default")
      (node (ref "U1") (pin "23") (pinfunction "P0.20/TRACECLK_23") (pintype "bidirectional+no_connect"))
    )
    (net (code "56") (name "unconnected-(U1-P0.29{slash}AN5-Pad41)") (class "Default")
      (node (ref "U1") (pin "41") (pinfunction "P0.29/AN5_41") (pintype "bidirectional+no_connect"))
    )
    (net (code "57") (name "unconnected-(U1-P0.31{slash}AN7-Pad43)") (class "Default")
      (node (ref "U1") (pin "43") (pinfunction "P0.31/AN7_43") (pintype "bidirectional+no_connect"))
    )
  )
)
